# arm.net
KiCad netlist of a schematic drawn in Altium Designer
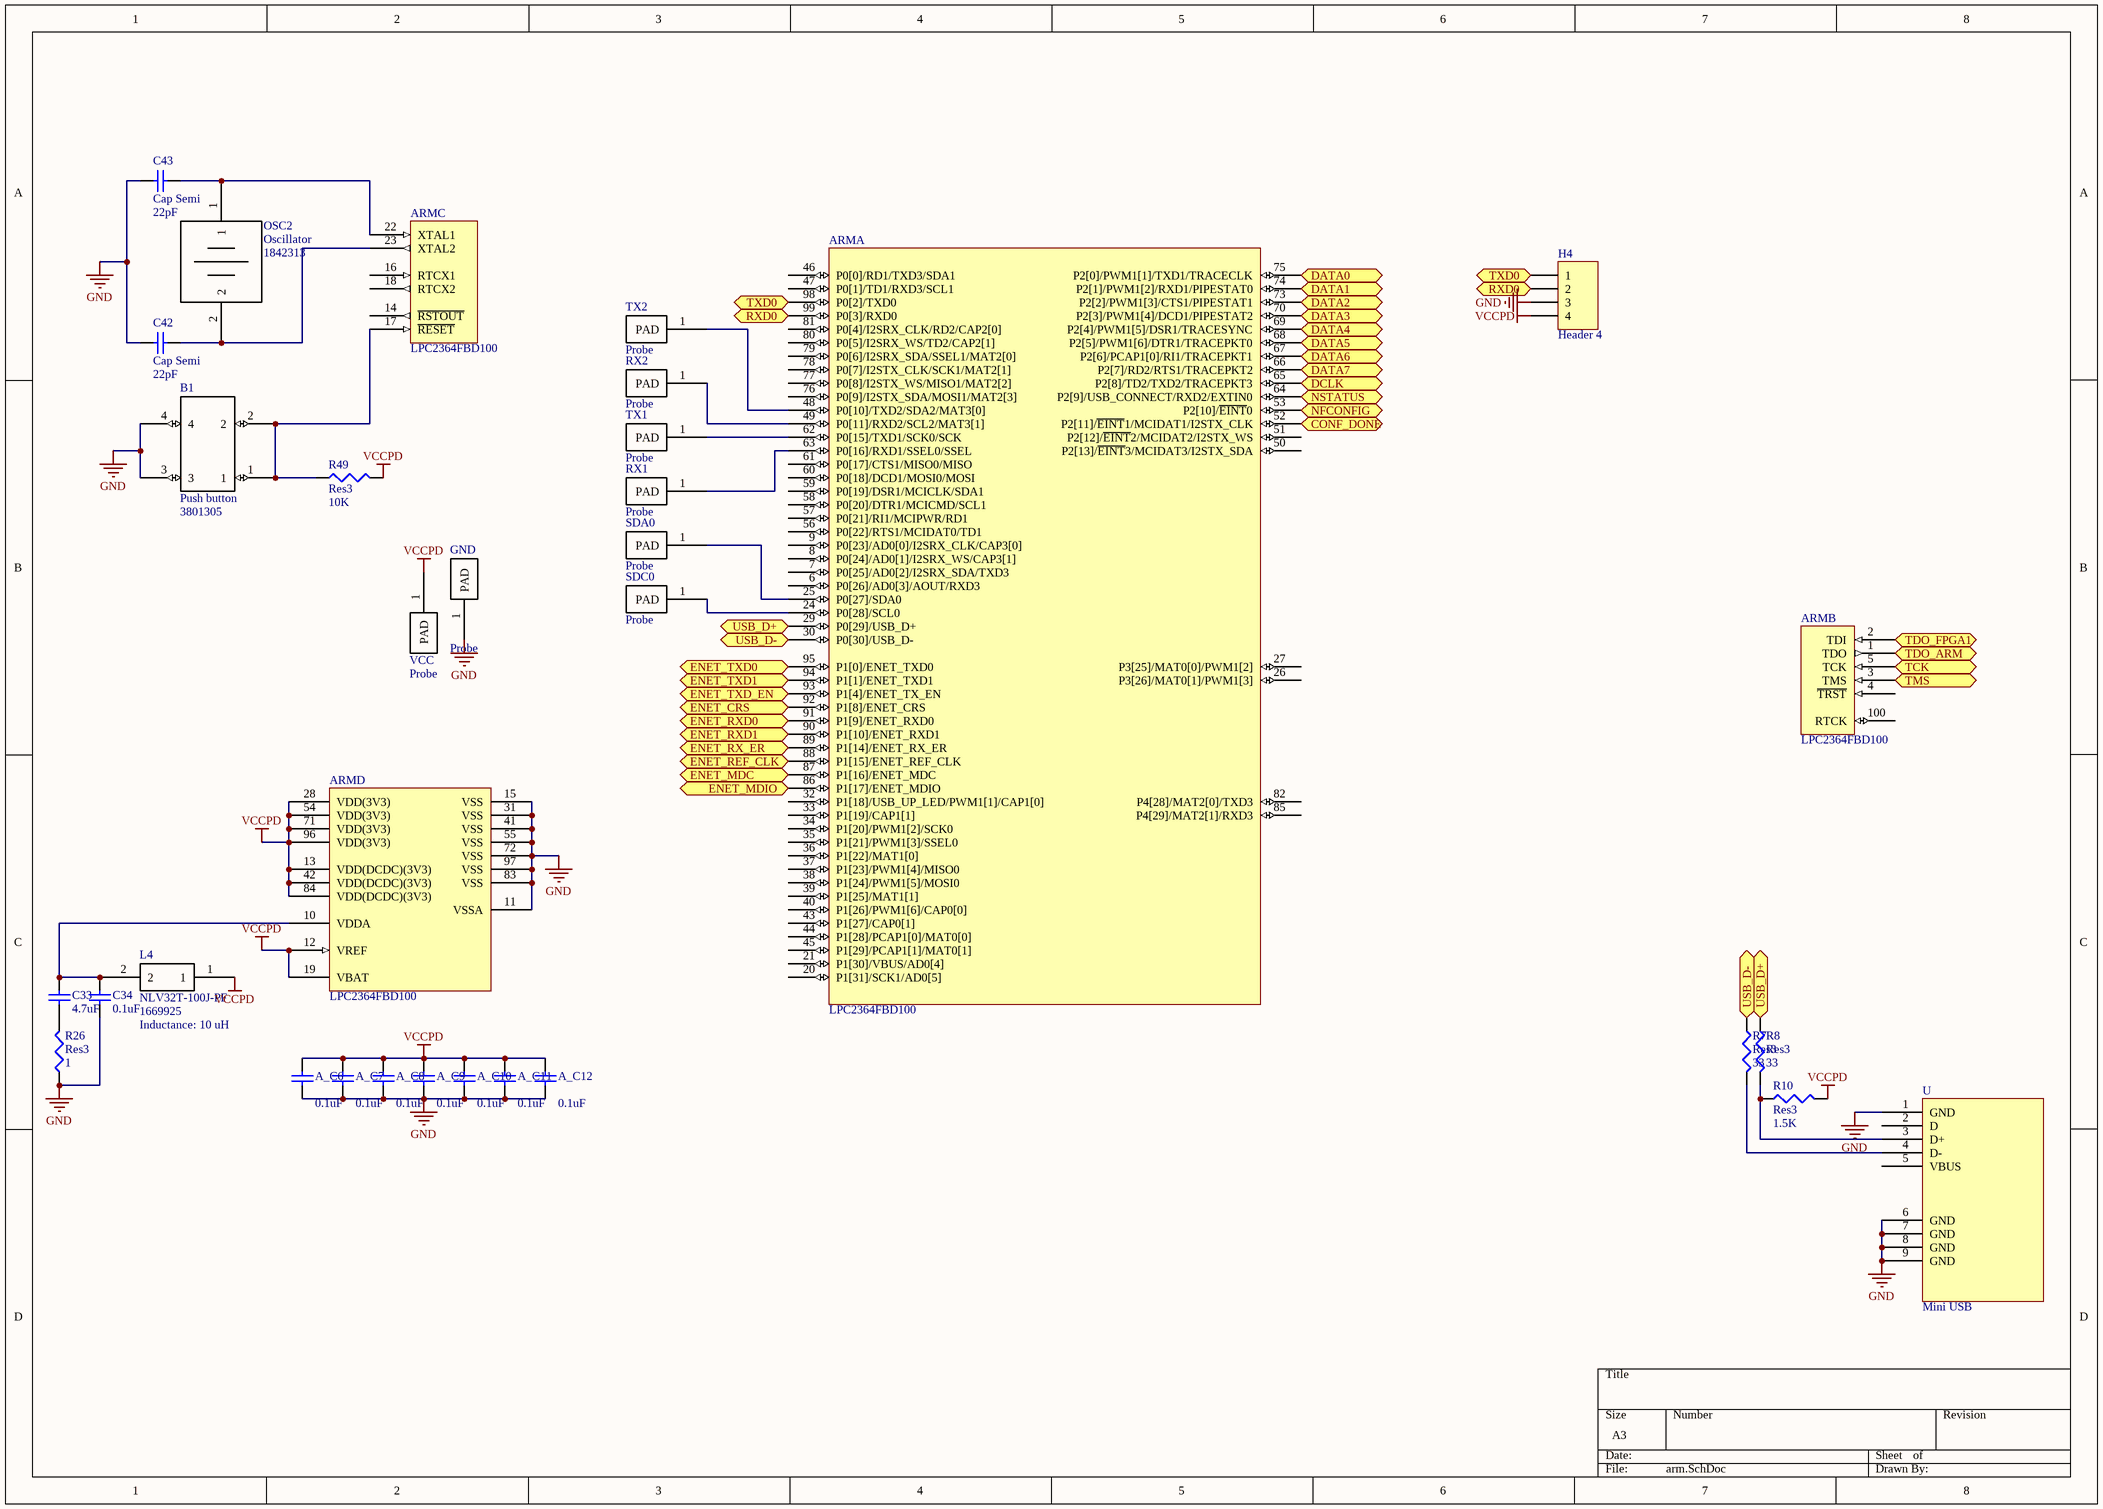
[diagram p0: arm.SchDoc]

(export (version "E")
  (design (tool "Eeschema 10.0.6"))
  (components
    (comp (ref "ARM")
      (value "LPC2364FBD100")
      (footprint "SOT407-1_N")
      (description "ARM7 16/32-Bit Microcontroller, 128KB Flash, 34KB RAM, 4 Channel CAN, 100-Lead LQFP")
      (fields (field (name "PUBLISHER") "Altium Limited"))
      (libsource (lib "NXP LPC2000") (part "LPC2364FBD100"))
    )
    (comp (ref "A_C6")
      (value "0.1uF")
      (footprint "CAPC1608L")
      (description "Capacitor (Semiconductor SIM Model)")
      (fields (field (name "Comment") "Cap Semi") (field (name "PUBLISHER") "Altium Limited"))
      (libsource (lib "Miscellaneous Devices") (part "Cap Semi"))
    )
    (comp (ref "A_C7")
      (value "0.1uF")
      (footprint "CAPC1608L")
      (description "Capacitor (Semiconductor SIM Model)")
      (fields (field (name "Comment") "Cap Semi") (field (name "PUBLISHER") "Altium Limited"))
      (libsource (lib "Miscellaneous Devices") (part "Cap Semi"))
    )
    (comp (ref "A_C8")
      (value "0.1uF")
      (footprint "CAPC1608L")
      (description "Capacitor (Semiconductor SIM Model)")
      (fields (field (name "Comment") "Cap Semi") (field (name "PUBLISHER") "Altium Limited"))
      (libsource (lib "Miscellaneous Devices") (part "Cap Semi"))
    )
    (comp (ref "A_C9")
      (value "0.1uF")
      (footprint "CAPC1608L")
      (description "Capacitor (Semiconductor SIM Model)")
      (fields (field (name "Comment") "Cap Semi") (field (name "PUBLISHER") "Altium Limited"))
      (libsource (lib "Miscellaneous Devices") (part "Cap Semi"))
    )
    (comp (ref "A_C10")
      (value "0.1uF")
      (footprint "CAPC1608L")
      (description "Capacitor (Semiconductor SIM Model)")
      (fields (field (name "Comment") "Cap Semi") (field (name "PUBLISHER") "Altium Limited"))
      (libsource (lib "Miscellaneous Devices") (part "Cap Semi"))
    )
    (comp (ref "A_C11")
      (value "0.1uF")
      (footprint "CAPC1608L")
      (description "Capacitor (Semiconductor SIM Model)")
      (fields (field (name "Comment") "Cap Semi") (field (name "PUBLISHER") "Altium Limited"))
      (libsource (lib "Miscellaneous Devices") (part "Cap Semi"))
    )
    (comp (ref "A_C12")
      (value "0.1uF")
      (footprint "CAPC1608L")
      (description "Capacitor (Semiconductor SIM Model)")
      (fields (field (name "Comment") "Cap Semi") (field (name "PUBLISHER") "Altium Limited"))
      (libsource (lib "Miscellaneous Devices") (part "Cap Semi"))
    )
    (comp (ref "B1")
      (value "Push button")
      (footprint "SMD Button")
      (fields (field (name "SUPPLIER PART NUMBER 1") "3801305"))
      (libsource (lib "Schematic Components") (part "Push button"))
    )
    (comp (ref "C33")
      (value "4.7uF")
      (footprint "CAPC1608L")
      (description "Capacitor (Semiconductor SIM Model)")
      (fields (field (name "Comment") "Cap Semi") (field (name "PUBLISHER") "Altium Limited"))
      (libsource (lib "Miscellaneous Devices") (part "Cap Semi"))
    )
    (comp (ref "C34")
      (value "0.1uF")
      (footprint "CAPC1608L")
      (description "Capacitor (Semiconductor SIM Model)")
      (fields (field (name "Comment") "Cap Semi") (field (name "PUBLISHER") "Altium Limited"))
      (libsource (lib "Miscellaneous Devices") (part "Cap Semi"))
    )
    (comp (ref "C42")
      (value "Cap Semi")
      (footprint "CAPC1608L")
      (description "Capacitor (Semiconductor SIM Model)")
      (fields (field (name "ALTIUM_VALUE") "22pF") (field (name "PUBLISHER") "Altium Limited"))
      (libsource (lib "Miscellaneous Devices") (part "Cap Semi"))
    )
    (comp (ref "C43")
      (value "Cap Semi")
      (footprint "CAPC1608L")
      (description "Capacitor (Semiconductor SIM Model)")
      (fields (field (name "ALTIUM_VALUE") "22pF") (field (name "PUBLISHER") "Altium Limited"))
      (libsource (lib "Miscellaneous Devices") (part "Cap Semi"))
    )
    (comp (ref "GND")
      (value "Probe")
      (footprint "Probe pad")
      (libsource (lib "Schematic Components") (part "Probe"))
    )
    (comp (ref "H4")
      (value "Header 4")
      (footprint "HDR1X4")
      (description "Header, 4-Pin")
      (fields (field (name "PUBLISHER") "Altium Limited"))
      (libsource (lib "Miscellaneous Connectors") (part "Header 4"))
    )
    (comp (ref "L4")
      (value "NLV32T-100J-PF")
      (footprint "INDC3225X22N")
      (fields (field (name "SUPPLIER PART NUMBER 1") "1669925") (field (name "INDUCTANCE") "10 uH"))
      (libsource (lib "Schematic Components") (part "NLV32T-100J-PF"))
    )
    (comp (ref "OSC2")
      (value "Oscillator")
      (footprint "HC49/4H_SMX")
      (fields (field (name "SUPPLIER PART NUMBER 1") "1842313"))
      (libsource (lib "Schematic Components") (part "Oscillator"))
    )
    (comp (ref "R7")
      (value "Res3")
      (footprint "RESC1608L")
      (description "Resistor")
      (fields (field (name "ALTIUM_VALUE") "33") (field (name "PUBLISHER") "Altium Limited"))
      (libsource (lib "Miscellaneous Devices") (part "Res3"))
    )
    (comp (ref "R8")
      (value "Res3")
      (footprint "RESC1608L")
      (description "Resistor")
      (fields (field (name "ALTIUM_VALUE") "33") (field (name "PUBLISHER") "Altium Limited"))
      (libsource (lib "Miscellaneous Devices") (part "Res3"))
    )
    (comp (ref "R10")
      (value "Res3")
      (footprint "RESC1608L")
      (description "Resistor")
      (fields (field (name "ALTIUM_VALUE") "1.5K") (field (name "PUBLISHER") "Altium Limited"))
      (libsource (lib "Miscellaneous Devices") (part "Res3"))
    )
    (comp (ref "R26")
      (value "Res3")
      (footprint "RESC1608L")
      (description "Resistor")
      (fields (field (name "ALTIUM_VALUE") "1") (field (name "PUBLISHER") "Altium Limited"))
      (libsource (lib "Miscellaneous Devices") (part "Res3"))
    )
    (comp (ref "R49")
      (value "Res3")
      (footprint "RESC1608L")
      (description "Resistor")
      (fields (field (name "ALTIUM_VALUE") "10K") (field (name "PUBLISHER") "Altium Limited"))
      (libsource (lib "Miscellaneous Devices") (part "Res3"))
    )
    (comp (ref "RX1")
      (value "Probe")
      (footprint "Probe pad")
      (libsource (lib "Schematic Components") (part "Probe"))
    )
    (comp (ref "RX2")
      (value "Probe")
      (footprint "Probe pad")
      (libsource (lib "Schematic Components") (part "Probe"))
    )
    (comp (ref "SDA0")
      (value "Probe")
      (footprint "Probe pad")
      (libsource (lib "Schematic Components") (part "Probe"))
    )
    (comp (ref "SDC0")
      (value "Probe")
      (footprint "Probe pad")
      (libsource (lib "Schematic Components") (part "Probe"))
    )
    (comp (ref "TX1")
      (value "Probe")
      (footprint "Probe pad")
      (libsource (lib "Schematic Components") (part "Probe"))
    )
    (comp (ref "TX2")
      (value "Probe")
      (footprint "Probe pad")
      (libsource (lib "Schematic Components") (part "Probe"))
    )
    (comp (ref "U")
      (value "Mini USB")
      (footprint "Mini USB B")
      (libsource (lib "Schematic Components") (part "Mini USB"))
    )
    (comp (ref "VCC")
      (value "Probe")
      (footprint "Probe pad")
      (libsource (lib "Schematic Components") (part "Probe"))
    )
  )
  (nets
    (net (code "1") (name "/CONF_DONE") (class "Default")
      (node (ref "ARM") (pin "52") (pinfunction "P2[11]/~{EINT}1/MCIDAT1/I2STX_CLK_52") (pintype "bidirectional"))
    )
    (net (code "2") (name "/DATA0") (class "Default")
      (node (ref "ARM") (pin "75") (pinfunction "P2[0]/PWM1[1]/TXD1/TRACECLK_75") (pintype "bidirectional"))
    )
    (net (code "3") (name "/DATA1") (class "Default")
      (node (ref "ARM") (pin "74") (pinfunction "P2[1]/PWM1[2]/RXD1/PIPESTAT0_74") (pintype "bidirectional"))
    )
    (net (code "4") (name "/DATA2") (class "Default")
      (node (ref "ARM") (pin "73") (pinfunction "P2[2]/PWM1[3]/CTS1/PIPESTAT1_73") (pintype "bidirectional"))
    )
    (net (code "5") (name "/DATA3") (class "Default")
      (node (ref "ARM") (pin "70") (pinfunction "P2[3]/PWM1[4]/DCD1/PIPESTAT2_70") (pintype "bidirectional"))
    )
    (net (code "6") (name "/DATA4") (class "Default")
      (node (ref "ARM") (pin "69") (pinfunction "P2[4]/PWM1[5]/DSR1/TRACESYNC_69") (pintype "bidirectional"))
    )
    (net (code "7") (name "/DATA5") (class "Default")
      (node (ref "ARM") (pin "68") (pinfunction "P2[5]/PWM1[6]/DTR1/TRACEPKT0_68") (pintype "bidirectional"))
    )
    (net (code "8") (name "/DATA6") (class "Default")
      (node (ref "ARM") (pin "67") (pinfunction "P2[6]/PCAP1[0]/RI1/TRACEPKT1_67") (pintype "bidirectional"))
    )
    (net (code "9") (name "/DATA7") (class "Default")
      (node (ref "ARM") (pin "66") (pinfunction "P2[7]/RD2/RTS1/TRACEPKT2_66") (pintype "bidirectional"))
    )
    (net (code "10") (name "/DCLK") (class "Default")
      (node (ref "ARM") (pin "65") (pinfunction "P2[8]/TD2/TXD2/TRACEPKT3_65") (pintype "bidirectional"))
    )
    (net (code "11") (name "/ENET_CRS") (class "Default")
      (node (ref "ARM") (pin "92") (pinfunction "P1[8]/ENET_CRS_92") (pintype "bidirectional"))
    )
    (net (code "12") (name "/ENET_MDC") (class "Default")
      (node (ref "ARM") (pin "87") (pinfunction "P1[16]/ENET_MDC_87") (pintype "bidirectional"))
    )
    (net (code "13") (name "/ENET_MDIO") (class "Default")
      (node (ref "ARM") (pin "86") (pinfunction "P1[17]/ENET_MDIO_86") (pintype "bidirectional"))
    )
    (net (code "14") (name "/ENET_REF_CLK") (class "Default")
      (node (ref "ARM") (pin "88") (pinfunction "P1[15]/ENET_REF_CLK_88") (pintype "bidirectional"))
    )
    (net (code "15") (name "/ENET_RXD0") (class "Default")
      (node (ref "ARM") (pin "91") (pinfunction "P1[9]/ENET_RXD0_91") (pintype "bidirectional"))
    )
    (net (code "16") (name "/ENET_RXD1") (class "Default")
      (node (ref "ARM") (pin "90") (pinfunction "P1[10]/ENET_RXD1_90") (pintype "bidirectional"))
    )
    (net (code "17") (name "/ENET_RX_ER") (class "Default")
      (node (ref "ARM") (pin "89") (pinfunction "P1[14]/ENET_RX_ER_89") (pintype "bidirectional"))
    )
    (net (code "18") (name "/ENET_TXD0") (class "Default")
      (node (ref "ARM") (pin "95") (pinfunction "P1[0]/ENET_TXD0_95") (pintype "bidirectional"))
    )
    (net (code "19") (name "/ENET_TXD1") (class "Default")
      (node (ref "ARM") (pin "94") (pinfunction "P1[1]/ENET_TXD1_94") (pintype "bidirectional"))
    )
    (net (code "20") (name "/ENET_TXD_EN") (class "Default")
      (node (ref "ARM") (pin "93") (pinfunction "P1[4]/ENET_TX_EN_93") (pintype "bidirectional"))
    )
    (net (code "21") (name "/NFCONFIG") (class "Default")
      (node (ref "ARM") (pin "53") (pinfunction "P2[10]/~{EINT}0_53") (pintype "bidirectional"))
    )
    (net (code "22") (name "/NSTATUS") (class "Default")
      (node (ref "ARM") (pin "64") (pinfunction "P2[9]/USB_CONNECT/RXD2/EXTIN0_64") (pintype "bidirectional"))
    )
    (net (code "23") (name "/RXD0") (class "Default")
      (node (ref "ARM") (pin "99") (pinfunction "P0[3]/RXD0_99") (pintype "bidirectional"))
      (node (ref "H4") (pin "2") (pinfunction "2_2") (pintype "passive"))
    )
    (net (code "24") (name "/TCK") (class "Default")
      (node (ref "ARM") (pin "5") (pinfunction "TCK_5") (pintype "input"))
    )
    (net (code "25") (name "/TDO_ARM") (class "Default")
      (node (ref "ARM") (pin "1") (pinfunction "TDO_1") (pintype "output"))
    )
    (net (code "26") (name "/TDO_FPGA1") (class "Default")
      (node (ref "ARM") (pin "2") (pinfunction "TDI_2") (pintype "input"))
    )
    (net (code "27") (name "/TMS") (class "Default")
      (node (ref "ARM") (pin "3") (pinfunction "TMS_3") (pintype "input"))
    )
    (net (code "28") (name "/TXD0") (class "Default")
      (node (ref "ARM") (pin "98") (pinfunction "P0[2]/TXD0_98") (pintype "bidirectional"))
      (node (ref "H4") (pin "1") (pinfunction "1_1") (pintype "passive"))
    )
    (net (code "29") (name "/USB_D+") (class "Default")
      (node (ref "ARM") (pin "29") (pinfunction "P0[29]/USB_D+_29") (pintype "bidirectional"))
      (node (ref "R8") (pin "1") (pinfunction "1_1") (pintype "passive"))
    )
    (net (code "30") (name "/USB_D-") (class "Default")
      (node (ref "ARM") (pin "30") (pinfunction "P0[30]/USB_D-_30") (pintype "bidirectional"))
      (node (ref "R7") (pin "1") (pinfunction "1_1") (pintype "passive"))
    )
    (net (code "31") (name "GND") (class "Default")
      (node (ref "ARM") (pin "11") (pinfunction "VSSA_11") (pintype "power_in"))
      (node (ref "ARM") (pin "15") (pinfunction "VSS_15") (pintype "power_in"))
      (node (ref "ARM") (pin "31") (pinfunction "VSS_31") (pintype "power_in"))
      (node (ref "ARM") (pin "41") (pinfunction "VSS_41") (pintype "power_in"))
      (node (ref "ARM") (pin "55") (pinfunction "VSS_55") (pintype "power_in"))
      (node (ref "ARM") (pin "72") (pinfunction "VSS_72") (pintype "power_in"))
      (node (ref "ARM") (pin "83") (pinfunction "VSS_83") (pintype "power_in"))
      (node (ref "ARM") (pin "97") (pinfunction "VSS_97") (pintype "power_in"))
      (node (ref "A_C10") (pin "2") (pinfunction "2_2") (pintype "passive"))
      (node (ref "A_C11") (pin "2") (pinfunction "2_2") (pintype "passive"))
      (node (ref "A_C12") (pin "2") (pinfunction "2_2") (pintype "passive"))
      (node (ref "A_C6") (pin "2") (pinfunction "2_2") (pintype "passive"))
      (node (ref "A_C7") (pin "2") (pinfunction "2_2") (pintype "passive"))
      (node (ref "A_C8") (pin "2") (pinfunction "2_2") (pintype "passive"))
      (node (ref "A_C9") (pin "2") (pinfunction "2_2") (pintype "passive"))
      (node (ref "B1") (pin "3") (pinfunction "3_3") (pintype "bidirectional"))
      (node (ref "B1") (pin "4") (pinfunction "4_4") (pintype "bidirectional"))
      (node (ref "C34") (pin "2") (pinfunction "2_2") (pintype "passive"))
      (node (ref "C42") (pin "1") (pinfunction "1_1") (pintype "passive"))
      (node (ref "C43") (pin "1") (pinfunction "1_1") (pintype "passive"))
      (node (ref "GND") (pin "1") (pinfunction "PAD_1") (pintype "power_in"))
      (node (ref "H4") (pin "3") (pinfunction "3_3") (pintype "passive"))
      (node (ref "R26") (pin "1") (pinfunction "1_1") (pintype "passive"))
      (node (ref "U") (pin "1") (pinfunction "GND_1") (pintype "power_in"))
      (node (ref "U") (pin "6") (pinfunction "GND_6") (pintype "power_in"))
      (node (ref "U") (pin "7") (pinfunction "GND_7") (pintype "power_in"))
      (node (ref "U") (pin "8") (pinfunction "GND_8") (pintype "power_in"))
      (node (ref "U") (pin "9") (pinfunction "GND_9") (pintype "power_in"))
    )
    (net (code "32") (name "Net-(ARMA-P0[10]{slash}TXD2{slash}SDA2{slash}MAT3[0])") (class "Default")
      (node (ref "ARM") (pin "48") (pinfunction "P0[10]/TXD2/SDA2/MAT3[0]_48") (pintype "bidirectional"))
      (node (ref "TX2") (pin "1") (pinfunction "PAD_1") (pintype "power_in"))
    )
    (net (code "33") (name "Net-(ARMA-P0[11]{slash}RXD2{slash}SCL2{slash}MAT3[1])") (class "Default")
      (node (ref "ARM") (pin "49") (pinfunction "P0[11]/RXD2/SCL2/MAT3[1]_49") (pintype "bidirectional"))
      (node (ref "RX2") (pin "1") (pinfunction "PAD_1") (pintype "power_in"))
    )
    (net (code "34") (name "Net-(ARMA-P0[15]{slash}TXD1{slash}SCK0{slash}SCK)") (class "Default")
      (node (ref "ARM") (pin "62") (pinfunction "P0[15]/TXD1/SCK0/SCK_62") (pintype "bidirectional"))
      (node (ref "TX1") (pin "1") (pinfunction "PAD_1") (pintype "power_in"))
    )
    (net (code "35") (name "Net-(ARMA-P0[16]{slash}RXD1{slash}SSEL0{slash}SSEL)") (class "Default")
      (node (ref "ARM") (pin "63") (pinfunction "P0[16]/RXD1/SSEL0/SSEL_63") (pintype "bidirectional"))
      (node (ref "RX1") (pin "1") (pinfunction "PAD_1") (pintype "power_in"))
    )
    (net (code "36") (name "Net-(ARMA-P0[27]{slash}SDA0)") (class "Default")
      (node (ref "ARM") (pin "25") (pinfunction "P0[27]/SDA0_25") (pintype "bidirectional"))
      (node (ref "SDA0") (pin "1") (pinfunction "PAD_1") (pintype "power_in"))
    )
    (net (code "37") (name "Net-(ARMA-P0[28]{slash}SCL0)") (class "Default")
      (node (ref "ARM") (pin "24") (pinfunction "P0[28]/SCL0_24") (pintype "bidirectional"))
      (node (ref "SDC0") (pin "1") (pinfunction "PAD_1") (pintype "power_in"))
    )
    (net (code "38") (name "Net-(ARMC-XTAL1)") (class "Default")
      (node (ref "ARM") (pin "22") (pinfunction "XTAL1_22") (pintype "input"))
      (node (ref "C43") (pin "2") (pinfunction "2_2") (pintype "passive"))
      (node (ref "OSC2") (pin "1") (pinfunction "1_1") (pintype "power_in"))
    )
    (net (code "39") (name "Net-(ARMC-XTAL2)") (class "Default")
      (node (ref "ARM") (pin "23") (pinfunction "XTAL2_23") (pintype "output"))
      (node (ref "C42") (pin "2") (pinfunction "2_2") (pintype "passive"))
      (node (ref "OSC2") (pin "2") (pinfunction "2_2") (pintype "power_in"))
    )
    (net (code "40") (name "Net-(ARMC-~{RESET})") (class "Default")
      (node (ref "ARM") (pin "17") (pinfunction "~{RESET}_17") (pintype "input"))
      (node (ref "B1") (pin "1") (pinfunction "1_1") (pintype "bidirectional"))
      (node (ref "B1") (pin "2") (pinfunction "2_2") (pintype "bidirectional"))
      (node (ref "R49") (pin "1") (pinfunction "1_1") (pintype "passive"))
    )
    (net (code "41") (name "Net-(ARMD-VDDA)") (class "Default")
      (node (ref "ARM") (pin "10") (pinfunction "VDDA_10") (pintype "power_in"))
      (node (ref "C33") (pin "1") (pinfunction "1_1") (pintype "passive"))
      (node (ref "C34") (pin "1") (pinfunction "1_1") (pintype "passive"))
      (node (ref "L4") (pin "2") (pinfunction "2_2") (pintype "power_in"))
    )
    (net (code "42") (name "Net-(C33-Pad2)") (class "Default")
      (node (ref "C33") (pin "2") (pinfunction "2_2") (pintype "passive"))
      (node (ref "R26") (pin "2") (pinfunction "2_2") (pintype "passive"))
    )
    (net (code "43") (name "Net-(U-D+)") (class "Default")
      (node (ref "R10") (pin "1") (pinfunction "1_1") (pintype "passive"))
      (node (ref "R8") (pin "2") (pinfunction "2_2") (pintype "passive"))
      (node (ref "U") (pin "3") (pinfunction "D+_3") (pintype "power_in"))
    )
    (net (code "44") (name "Net-(U-D-)") (class "Default")
      (node (ref "R7") (pin "2") (pinfunction "2_2") (pintype "passive"))
      (node (ref "U") (pin "4") (pinfunction "D-_4") (pintype "power_in"))
    )
    (net (code "45") (name "VCCPD") (class "Default")
      (node (ref "ARM") (pin "12") (pinfunction "VREF_12") (pintype "input"))
      (node (ref "ARM") (pin "13") (pinfunction "VDD(DCDC)(3V3)_13") (pintype "power_in"))
      (node (ref "ARM") (pin "19") (pinfunction "VBAT_19") (pintype "power_in"))
      (node (ref "ARM") (pin "28") (pinfunction "VDD(3V3)_28") (pintype "power_in"))
      (node (ref "ARM") (pin "42") (pinfunction "VDD(DCDC)(3V3)_42") (pintype "power_in"))
      (node (ref "ARM") (pin "54") (pinfunction "VDD(3V3)_54") (pintype "power_in"))
      (node (ref "ARM") (pin "71") (pinfunction "VDD(3V3)_71") (pintype "power_in"))
      (node (ref "ARM") (pin "84") (pinfunction "VDD(DCDC)(3V3)_84") (pintype "power_in"))
      (node (ref "ARM") (pin "96") (pinfunction "VDD(3V3)_96") (pintype "power_in"))
      (node (ref "A_C10") (pin "1") (pinfunction "1_1") (pintype "passive"))
      (node (ref "A_C11") (pin "1") (pinfunction "1_1") (pintype "passive"))
      (node (ref "A_C12") (pin "1") (pinfunction "1_1") (pintype "passive"))
      (node (ref "A_C6") (pin "1") (pinfunction "1_1") (pintype "passive"))
      (node (ref "A_C7") (pin "1") (pinfunction "1_1") (pintype "passive"))
      (node (ref "A_C8") (pin "1") (pinfunction "1_1") (pintype "passive"))
      (node (ref "A_C9") (pin "1") (pinfunction "1_1") (pintype "passive"))
      (node (ref "H4") (pin "4") (pinfunction "4_4") (pintype "passive"))
      (node (ref "L4") (pin "1") (pinfunction "1_1") (pintype "power_in"))
      (node (ref "R10") (pin "2") (pinfunction "2_2") (pintype "passive"))
      (node (ref "R49") (pin "2") (pinfunction "2_2") (pintype "passive"))
      (node (ref "VCC") (pin "1") (pinfunction "PAD_1") (pintype "power_in"))
    )
    (net (code "46") (name "unconnected-(ARMA-P0[0]{slash}RD1{slash}TXD3{slash}SDA1-Pad46)") (class "Default")
      (node (ref "ARM") (pin "46") (pinfunction "P0[0]/RD1/TXD3/SDA1_46") (pintype "bidirectional"))
    )
    (net (code "47") (name "unconnected-(ARMA-P0[1]{slash}TD1{slash}RXD3{slash}SCL1-Pad47)") (class "Default")
      (node (ref "ARM") (pin "47") (pinfunction "P0[1]/TD1/RXD3/SCL1_47") (pintype "bidirectional"))
    )
    (net (code "48") (name "unconnected-(ARMA-P0[4]{slash}I2SRX_CLK{slash}RD2{slash}CAP2[0]-Pad81)") (class "Default")
      (node (ref "ARM") (pin "81") (pinfunction "P0[4]/I2SRX_CLK/RD2/CAP2[0]_81") (pintype "bidirectional"))
    )
    (net (code "49") (name "unconnected-(ARMA-P0[5]{slash}I2SRX_WS{slash}TD2{slash}CAP2[1]-Pad80)") (class "Default")
      (node (ref "ARM") (pin "80") (pinfunction "P0[5]/I2SRX_WS/TD2/CAP2[1]_80") (pintype "bidirectional"))
    )
    (net (code "50") (name "unconnected-(ARMA-P0[6]{slash}I2SRX_SDA{slash}SSEL1{slash}MAT2[0]-Pad79)") (class "Default")
      (node (ref "ARM") (pin "79") (pinfunction "P0[6]/I2SRX_SDA/SSEL1/MAT2[0]_79") (pintype "bidirectional"))
    )
    (net (code "51") (name "unconnected-(ARMA-P0[7]{slash}I2STX_CLK{slash}SCK1{slash}MAT2[1]-Pad78)") (class "Default")
      (node (ref "ARM") (pin "78") (pinfunction "P0[7]/I2STX_CLK/SCK1/MAT2[1]_78") (pintype "bidirectional"))
    )
    (net (code "52") (name "unconnected-(ARMA-P0[8]{slash}I2STX_WS{slash}MISO1{slash}MAT2[2]-Pad77)") (class "Default")
      (node (ref "ARM") (pin "77") (pinfunction "P0[8]/I2STX_WS/MISO1/MAT2[2]_77") (pintype "bidirectional"))
    )
    (net (code "53") (name "unconnected-(ARMA-P0[9]{slash}I2STX_SDA{slash}MOSI1{slash}MAT2[3]-Pad76)") (class "Default")
      (node (ref "ARM") (pin "76") (pinfunction "P0[9]/I2STX_SDA/MOSI1/MAT2[3]_76") (pintype "bidirectional"))
    )
    (net (code "54") (name "unconnected-(ARMA-P0[17]{slash}CTS1{slash}MISO0{slash}MISO-Pad61)") (class "Default")
      (node (ref "ARM") (pin "61") (pinfunction "P0[17]/CTS1/MISO0/MISO_61") (pintype "bidirectional"))
    )
    (net (code "55") (name "unconnected-(ARMA-P0[18]{slash}DCD1{slash}MOSI0{slash}MOSI-Pad60)") (class "Default")
      (node (ref "ARM") (pin "60") (pinfunction "P0[18]/DCD1/MOSI0/MOSI_60") (pintype "bidirectional"))
    )
    (net (code "56") (name "unconnected-(ARMA-P0[19]{slash}DSR1{slash}MCICLK{slash}SDA1-Pad59)") (class "Default")
      (node (ref "ARM") (pin "59") (pinfunction "P0[19]/DSR1/MCICLK/SDA1_59") (pintype "bidirectional"))
    )
    (net (code "57") (name "unconnected-(ARMA-P0[20]{slash}DTR1{slash}MCICMD{slash}SCL1-Pad58)") (class "Default")
      (node (ref "ARM") (pin "58") (pinfunction "P0[20]/DTR1/MCICMD/SCL1_58") (pintype "bidirectional"))
    )
    (net (code "58") (name "unconnected-(ARMA-P0[21]{slash}RI1{slash}MCIPWR{slash}RD1-Pad57)") (class "Default")
      (node (ref "ARM") (pin "57") (pinfunction "P0[21]/RI1/MCIPWR/RD1_57") (pintype "bidirectional"))
    )
    (net (code "59") (name "unconnected-(ARMA-P0[22]{slash}RTS1{slash}MCIDAT0{slash}TD1-Pad56)") (class "Default")
      (node (ref "ARM") (pin "56") (pinfunction "P0[22]/RTS1/MCIDAT0/TD1_56") (pintype "bidirectional"))
    )
    (net (code "60") (name "unconnected-(ARMA-P0[23]{slash}AD0[0]{slash}I2SRX_CLK{slash}CAP3[0]-Pad9)") (class "Default")
      (node (ref "ARM") (pin "9") (pinfunction "P0[23]/AD0[0]/I2SRX_CLK/CAP3[0]_9") (pintype "bidirectional"))
    )
    (net (code "61") (name "unconnected-(ARMA-P0[24]{slash}AD0[1]{slash}I2SRX_WS{slash}CAP3[1]-Pad8)") (class "Default")
      (node (ref "ARM") (pin "8") (pinfunction "P0[24]/AD0[1]/I2SRX_WS/CAP3[1]_8") (pintype "bidirectional"))
    )
    (net (code "62") (name "unconnected-(ARMA-P0[25]{slash}AD0[2]{slash}I2SRX_SDA{slash}TXD3-Pad7)") (class "Default")
      (node (ref "ARM") (pin "7") (pinfunction "P0[25]/AD0[2]/I2SRX_SDA/TXD3_7") (pintype "bidirectional"))
    )
    (net (code "63") (name "unconnected-(ARMA-P0[26]{slash}AD0[3]{slash}AOUT{slash}RXD3-Pad6)") (class "Default")
      (node (ref "ARM") (pin "6") (pinfunction "P0[26]/AD0[3]/AOUT/RXD3_6") (pintype "bidirectional"))
    )
    (net (code "64") (name "unconnected-(ARMA-P1[18]{slash}USB_UP_LED{slash}PWM1[1]{slash}CAP1[0]-Pad32)") (class "Default")
      (node (ref "ARM") (pin "32") (pinfunction "P1[18]/USB_UP_LED/PWM1[1]/CAP1[0]_32") (pintype "bidirectional"))
    )
    (net (code "65") (name "unconnected-(ARMA-P1[19]{slash}CAP1[1]-Pad33)") (class "Default")
      (node (ref "ARM") (pin "33") (pinfunction "P1[19]/CAP1[1]_33") (pintype "bidirectional"))
    )
    (net (code "66") (name "unconnected-(ARMA-P1[20]{slash}PWM1[2]{slash}SCK0-Pad34)") (class "Default")
      (node (ref "ARM") (pin "34") (pinfunction "P1[20]/PWM1[2]/SCK0_34") (pintype "bidirectional"))
    )
    (net (code "67") (name "unconnected-(ARMA-P1[21]{slash}PWM1[3]{slash}SSEL0-Pad35)") (class "Default")
      (node (ref "ARM") (pin "35") (pinfunction "P1[21]/PWM1[3]/SSEL0_35") (pintype "bidirectional"))
    )
    (net (code "68") (name "unconnected-(ARMA-P1[22]{slash}MAT1[0]-Pad36)") (class "Default")
      (node (ref "ARM") (pin "36") (pinfunction "P1[22]/MAT1[0]_36") (pintype "bidirectional"))
    )
    (net (code "69") (name "unconnected-(ARMA-P1[23]{slash}PWM1[4]{slash}MISO0-Pad37)") (class "Default")
      (node (ref "ARM") (pin "37") (pinfunction "P1[23]/PWM1[4]/MISO0_37") (pintype "bidirectional"))
    )
    (net (code "70") (name "unconnected-(ARMA-P1[24]{slash}PWM1[5]{slash}MOSI0-Pad38)") (class "Default")
      (node (ref "ARM") (pin "38") (pinfunction "P1[24]/PWM1[5]/MOSI0_38") (pintype "bidirectional"))
    )
    (net (code "71") (name "unconnected-(ARMA-P1[25]{slash}MAT1[1]-Pad39)") (class "Default")
      (node (ref "ARM") (pin "39") (pinfunction "P1[25]/MAT1[1]_39") (pintype "bidirectional"))
    )
    (net (code "72") (name "unconnected-(ARMA-P1[26]{slash}PWM1[6]{slash}CAP0[0]-Pad40)") (class "Default")
      (node (ref "ARM") (pin "40") (pinfunction "P1[26]/PWM1[6]/CAP0[0]_40") (pintype "bidirectional"))
    )
    (net (code "73") (name "unconnected-(ARMA-P1[27]{slash}CAP0[1]-Pad43)") (class "Default")
      (node (ref "ARM") (pin "43") (pinfunction "P1[27]/CAP0[1]_43") (pintype "bidirectional"))
    )
    (net (code "74") (name "unconnected-(ARMA-P1[28]{slash}PCAP1[0]{slash}MAT0[0]-Pad44)") (class "Default")
      (node (ref "ARM") (pin "44") (pinfunction "P1[28]/PCAP1[0]/MAT0[0]_44") (pintype "bidirectional"))
    )
    (net (code "75") (name "unconnected-(ARMA-P1[29]{slash}PCAP1[1]{slash}MAT0[1]-Pad45)") (class "Default")
      (node (ref "ARM") (pin "45") (pinfunction "P1[29]/PCAP1[1]/MAT0[1]_45") (pintype "bidirectional"))
    )
    (net (code "76") (name "unconnected-(ARMA-P1[30]{slash}VBUS{slash}AD0[4]-Pad21)") (class "Default")
      (node (ref "ARM") (pin "21") (pinfunction "P1[30]/VBUS/AD0[4]_21") (pintype "bidirectional"))
    )
    (net (code "77") (name "unconnected-(ARMA-P1[31]{slash}SCK1{slash}AD0[5]-Pad20)") (class "Default")
      (node (ref "ARM") (pin "20") (pinfunction "P1[31]/SCK1/AD0[5]_20") (pintype "bidirectional"))
    )
    (net (code "78") (name "unconnected-(ARMA-P2[12]{slash}~{EINT}2{slash}MCIDAT2{slash}I2STX_WS-Pad51)") (class "Default")
      (node (ref "ARM") (pin "51") (pinfunction "P2[12]/~{EINT}2/MCIDAT2/I2STX_WS_51") (pintype "bidirectional"))
    )
    (net (code "79") (name "unconnected-(ARMA-P2[13]{slash}~{EINT}3{slash}MCIDAT3{slash}I2STX_SDA-Pad50)") (class "Default")
      (node (ref "ARM") (pin "50") (pinfunction "P2[13]/~{EINT}3/MCIDAT3/I2STX_SDA_50") (pintype "bidirectional"))
    )
    (net (code "80") (name "unconnected-(ARMA-P3[25]{slash}MAT0[0]{slash}PWM1[2]-Pad27)") (class "Default")
      (node (ref "ARM") (pin "27") (pinfunction "P3[25]/MAT0[0]/PWM1[2]_27") (pintype "bidirectional"))
    )
    (net (code "81") (name "unconnected-(ARMA-P3[26]{slash}MAT0[1]{slash}PWM1[3]-Pad26)") (class "Default")
      (node (ref "ARM") (pin "26") (pinfunction "P3[26]/MAT0[1]/PWM1[3]_26") (pintype "bidirectional"))
    )
    (net (code "82") (name "unconnected-(ARMA-P4[28]{slash}MAT2[0]{slash}TXD3-Pad82)") (class "Default")
      (node (ref "ARM") (pin "82") (pinfunction "P4[28]/MAT2[0]/TXD3_82") (pintype "bidirectional"))
    )
    (net (code "83") (name "unconnected-(ARMA-P4[29]{slash}MAT2[1]{slash}RXD3-Pad85)") (class "Default")
      (node (ref "ARM") (pin "85") (pinfunction "P4[29]/MAT2[1]/RXD3_85") (pintype "bidirectional"))
    )
    (net (code "84") (name "unconnected-(ARMB-RTCK-Pad100)") (class "Default")
      (node (ref "ARM") (pin "100") (pinfunction "RTCK_100") (pintype "bidirectional"))
    )
    (net (code "85") (name "unconnected-(ARMB-~{TRST}-Pad4)") (class "Default")
      (node (ref "ARM") (pin "4") (pinfunction "~{TRST}_4") (pintype "input"))
    )
    (net (code "86") (name "unconnected-(ARMC-RTCX1-Pad16)") (class "Default")
      (node (ref "ARM") (pin "16") (pinfunction "RTCX1_16") (pintype "input"))
    )
    (net (code "87") (name "unconnected-(ARMC-RTCX2-Pad18)") (class "Default")
      (node (ref "ARM") (pin "18") (pinfunction "RTCX2_18") (pintype "output"))
    )
    (net (code "88") (name "unconnected-(ARMC-~{RSTOUT}-Pad14)") (class "Default")
      (node (ref "ARM") (pin "14") (pinfunction "~{RSTOUT}_14") (pintype "output"))
    )
    (net (code "89") (name "unconnected-(U-D-Pad2)") (class "Default")
      (node (ref "U") (pin "2") (pinfunction "D_2") (pintype "power_in"))
    )
    (net (code "90") (name "unconnected-(U-VBUS-Pad5)") (class "Default")
      (node (ref "U") (pin "5") (pinfunction "VBUS_5") (pintype "power_in"))
    )
  )
)
